# BjtPhaseShiftOsc.net
KiCad netlist of a schematic drawn in Altium Designer
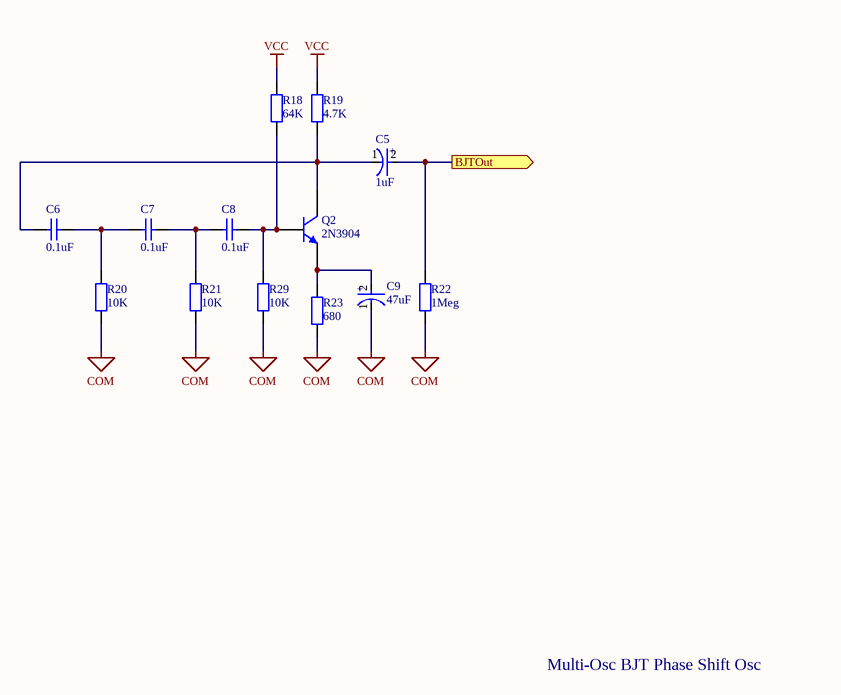
[diagram p0: BjtPhaseShiftOsc.SchDoc]

(export (version "E")
  (design (tool "Eeschema 10.0.6"))
  (components
    (comp (ref "C5")
      (value "1uF")
      (footprint "FP-ESLE3-MFG")
      (description "CAP ALUM 10UF 20% 100V THRU HOLE")
      (fields (field (name "TOLERANCE") "20%") (field (name "MANUFACTURER PART NUMBER") "ESL106M100AE3AA"))
      (libsource (lib "Altium Content Vault") (part "cf48714ba7e38822c1575c7ec0b6d1f"))
    )
    (comp (ref "C6")
      (value "0.1uF")
      (footprint "KEMT-C315-THT-2")
      (description "Capacitor, Ceramic, 0.01 uF, +/- 10%, 100 V, X7R, -55 to 125 degC, 2-Pin THD, RoHS, Bulk")
      (libsource (lib "Altium Content Vault") (part "CAP-NP-2"))
    )
    (comp (ref "C7")
      (value "0.1uF")
      (footprint "KEMT-C315-THT-2")
      (description "Capacitor, Ceramic, 0.01 uF, +/- 10%, 100 V, X7R, -55 to 125 degC, 2-Pin THD, RoHS, Bulk")
      (libsource (lib "Altium Content Vault") (part "CAP-NP-2"))
    )
    (comp (ref "C8")
      (value "0.1uF")
      (footprint "KEMT-C315-THT-2")
      (description "Capacitor, Ceramic, 0.01 uF, +/- 10%, 100 V, X7R, -55 to 125 degC, 2-Pin THD, RoHS, Bulk")
      (libsource (lib "Altium Content Vault") (part "CAP-NP-2"))
    )
    (comp (ref "C9")
      (value "47uF")
      (footprint "FP-ESLE3-MFG")
      (description "CAP ALUM 10UF 20% 100V THRU HOLE")
      (fields (field (name "TOLERANCE") "20%") (field (name "MANUFACTURER PART NUMBER") "ESL106M100AE3AA"))
      (libsource (lib "Altium Content Vault") (part "cf48714ba7e38822c1575c7ec0b6d1f"))
    )
    (comp (ref "Q2")
      (value "2N3904")
      (footprint "TO-92A")
      (description "NPN General Purpose Amplifier")
      (fields (field (name "PUBLISHER") "Altium Limited"))
      (libsource (lib "Miscellaneous Devices") (part "2N3904"))
    )
    (comp (ref "R18")
      (value "64K")
      (footprint "AXIAL-0.4")
      (description "Resistor")
      (fields (field (name "PUBLISHER") "Altium Limited"))
      (libsource (lib "Miscellaneous Devices") (part "Res2"))
    )
    (comp (ref "R19")
      (value "4.7K")
      (footprint "AXIAL-0.4")
      (description "Resistor")
      (fields (field (name "PUBLISHER") "Altium Limited"))
      (libsource (lib "") (part "Res2_1"))
    )
    (comp (ref "R20")
      (value "10K")
      (footprint "AXIAL-0.4")
      (description "Resistor")
      (fields (field (name "PUBLISHER") "Altium Limited"))
      (libsource (lib "") (part "Res2_1"))
    )
    (comp (ref "R21")
      (value "10K")
      (footprint "AXIAL-0.4")
      (description "Resistor")
      (fields (field (name "PUBLISHER") "Altium Limited"))
      (libsource (lib "") (part "Res2_1"))
    )
    (comp (ref "R22")
      (value "1Meg")
      (footprint "AXIAL-0.4")
      (description "Resistor")
      (fields (field (name "PUBLISHER") "Altium Limited"))
      (libsource (lib "") (part "Res2_1"))
    )
    (comp (ref "R23")
      (value "680")
      (footprint "AXIAL-0.4")
      (description "Resistor")
      (fields (field (name "PUBLISHER") "Altium Limited"))
      (libsource (lib "") (part "Res2_1"))
    )
    (comp (ref "R29")
      (value "10K")
      (footprint "AXIAL-0.4")
      (description "Resistor")
      (fields (field (name "PUBLISHER") "Altium Limited"))
      (libsource (lib "") (part "Res2_1"))
    )
  )
  (nets
    (net (code "1") (name "/BJTOut") (class "Default")
      (node (ref "C5") (pin "2") (pinfunction "A_2") (pintype "passive"))
      (node (ref "R22") (pin "1") (pinfunction "1_1") (pintype "passive"))
    )
    (net (code "2") (name "COM") (class "Default")
      (node (ref "C9") (pin "1") (pinfunction "C_1") (pintype "passive"))
      (node (ref "R20") (pin "2") (pinfunction "2_2") (pintype "passive"))
      (node (ref "R21") (pin "2") (pinfunction "2_2") (pintype "passive"))
      (node (ref "R22") (pin "2") (pinfunction "2_2") (pintype "passive"))
      (node (ref "R23") (pin "2") (pinfunction "2_2") (pintype "passive"))
      (node (ref "R29") (pin "2") (pinfunction "2_2") (pintype "passive"))
    )
    (net (code "3") (name "Net-(C5-C)") (class "Default")
      (node (ref "C5") (pin "1") (pinfunction "C_1") (pintype "passive"))
      (node (ref "C6") (pin "2") (pinfunction "2_2") (pintype "passive"))
      (node (ref "Q2") (pin "3") (pinfunction "C_3") (pintype "passive"))
      (node (ref "R19") (pin "2") (pinfunction "2_2") (pintype "passive"))
    )
    (net (code "4") (name "Net-(C6-Pad1)") (class "Default")
      (node (ref "C6") (pin "1") (pinfunction "1_1") (pintype "passive"))
      (node (ref "C7") (pin "2") (pinfunction "2_2") (pintype "passive"))
      (node (ref "R20") (pin "1") (pinfunction "1_1") (pintype "passive"))
    )
    (net (code "5") (name "Net-(C7-Pad1)") (class "Default")
      (node (ref "C7") (pin "1") (pinfunction "1_1") (pintype "passive"))
      (node (ref "C8") (pin "1") (pinfunction "1_1") (pintype "passive"))
      (node (ref "R21") (pin "1") (pinfunction "1_1") (pintype "passive"))
    )
    (net (code "6") (name "Net-(C9-A)") (class "Default")
      (node (ref "C9") (pin "2") (pinfunction "A_2") (pintype "passive"))
      (node (ref "Q2") (pin "1") (pinfunction "E_1") (pintype "passive"))
      (node (ref "R23") (pin "1") (pinfunction "1_1") (pintype "passive"))
    )
    (net (code "7") (name "Net-(Q2-B)") (class "Default")
      (node (ref "C8") (pin "2") (pinfunction "2_2") (pintype "passive"))
      (node (ref "Q2") (pin "2") (pinfunction "B_2") (pintype "passive"))
      (node (ref "R18") (pin "1") (pinfunction "1_1") (pintype "passive"))
      (node (ref "R29") (pin "1") (pinfunction "1_1") (pintype "passive"))
    )
    (net (code "8") (name "VCC") (class "Default")
      (node (ref "R18") (pin "2") (pinfunction "2_2") (pintype "passive"))
      (node (ref "R19") (pin "1") (pinfunction "1_1") (pintype "passive"))
    )
  )
)
